# laser.net
KiCad netlist of a schematic drawn in EAGLE
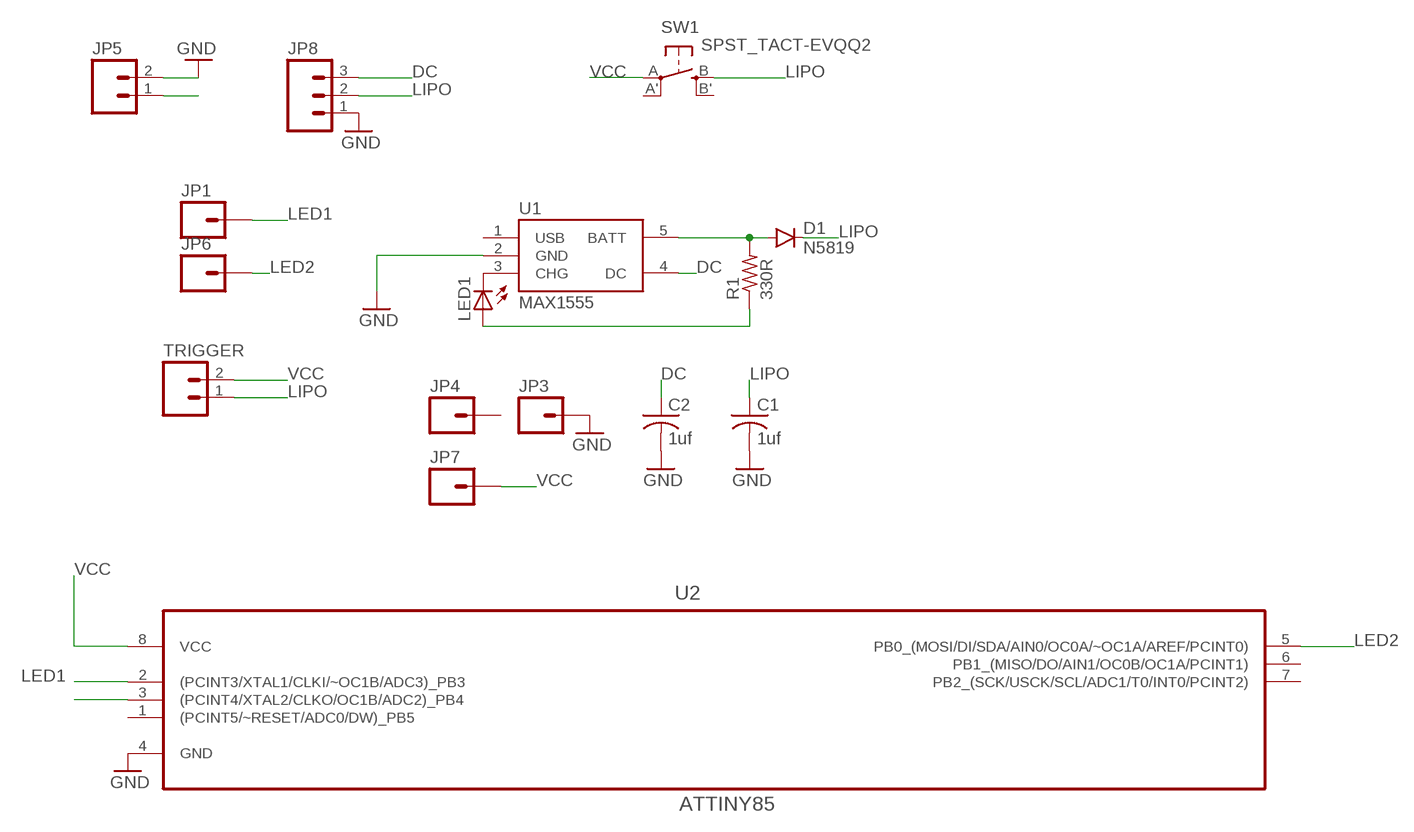
[diagram p0: schematic, sheet 1]

(export (version "E")
  (design (tool "Eeschema 10.0.6"))
  (components
    (comp (ref "C1")
      (value "1uf")
      (footprint "eagle-import:C0805K")
      (libsource (lib "eagle-import") (part "C-USC0805K"))
    )
    (comp (ref "C2")
      (value "1uf")
      (footprint "eagle-import:C0805K")
      (libsource (lib "eagle-import") (part "C-USC0805K"))
    )
    (comp (ref "D1")
      (value "N5819")
      (footprint "eagle-import:DIODE-1N4148")
      (libsource (lib "eagle-import") (part "DIODE1N4148"))
    )
    (comp (ref "JP1")
      (value "M01PTH")
      (footprint "eagle-import:1X01")
      (libsource (lib "eagle-import") (part "M01PTH"))
    )
    (comp (ref "JP3")
      (value "M01PTH")
      (footprint "eagle-import:1X01")
      (libsource (lib "eagle-import") (part "M01PTH"))
    )
    (comp (ref "JP4")
      (value "M01PTH")
      (footprint "eagle-import:1X01")
      (libsource (lib "eagle-import") (part "M01PTH"))
    )
    (comp (ref "JP5")
      (value "M02LOCK")
      (footprint "eagle-import:1X02_LOCK")
      (libsource (lib "eagle-import") (part "M02LOCK"))
    )
    (comp (ref "JP6")
      (value "M01PTH")
      (footprint "eagle-import:1X01")
      (libsource (lib "eagle-import") (part "M01PTH"))
    )
    (comp (ref "JP7")
      (value "M01PTH")
      (footprint "eagle-import:1X01")
      (libsource (lib "eagle-import") (part "M01PTH"))
    )
    (comp (ref "JP8")
      (value "M03LOCK")
      (footprint "eagle-import:1X03_LOCK")
      (libsource (lib "eagle-import") (part "M03LOCK"))
    )
    (comp (ref "LED1")
      (value "LEDCHIP-LED0805")
      (footprint "eagle-import:CHIP-LED0805")
      (libsource (lib "eagle-import") (part "LEDCHIP-LED0805"))
    )
    (comp (ref "R1")
      (value "330R")
      (footprint "eagle-import:M0805")
      (libsource (lib "eagle-import") (part "R-US_M0805"))
    )
    (comp (ref "SW1")
      (value "SPST_TACT-EVQQ2")
      (footprint "eagle-import:EVQ-Q2")
      (libsource (lib "eagle-import") (part "SPST_TACT-EVQQ2"))
    )
    (comp (ref "TRIGGER")
      (value "M02PTH")
      (footprint "eagle-import:1X02")
      (libsource (lib "eagle-import") (part "M02PTH"))
    )
    (comp (ref "U1")
      (value "MAX1555")
      (footprint "eagle-import:SOT23-5")
      (libsource (lib "eagle-import") (part "MAX1555"))
    )
    (comp (ref "U2")
      (value "ATTINY85")
      (footprint "eagle-import:DIP254P762X533-8")
      (fields (field (name "MPN") "ATTINY85-20PU"))
      (libsource (lib "eagle-import") (part "ATTINY85-20PU"))
    )
  )
  (nets
    (net (code "1") (name "/DC") (class "Default")
      (node (ref "C2") (pin "1") (pinfunction "1_1") (pintype "passive"))
      (node (ref "JP8") (pin "3") (pinfunction "3_3") (pintype "passive"))
      (node (ref "U1") (pin "4") (pinfunction "DC_4") (pintype "bidirectional"))
    )
    (net (code "2") (name "/LED1") (class "Default")
      (node (ref "JP1") (pin "1") (pinfunction "1_1") (pintype "passive"))
      (node (ref "U2") (pin "2") (pinfunction "(PCINT3/XTAL1/CLKI/~{OC1B/ADC3})_PB3_2") (pintype "bidirectional"))
    )
    (net (code "3") (name "/LED2") (class "Default")
      (node (ref "JP6") (pin "1") (pinfunction "1_1") (pintype "passive"))
      (node (ref "U2") (pin "5") (pinfunction "PB0_(MOSI/DI/SDA/AIN0/OC0A/~{OC1A/AREF/PCINT0})_5") (pintype "bidirectional"))
    )
    (net (code "4") (name "/LIPO") (class "Default")
      (node (ref "C1") (pin "1") (pinfunction "1_1") (pintype "passive"))
      (node (ref "D1") (pin "C") (pinfunction "C_C") (pintype "passive"))
      (node (ref "JP8") (pin "2") (pinfunction "2_2") (pintype "passive"))
      (node (ref "SW1") (pin "B") (pinfunction "S_B") (pintype "passive"))
      (node (ref "TRIGGER") (pin "1") (pinfunction "1_1") (pintype "passive"))
    )
    (net (code "5") (name "/TONE") (class "Default")
      (node (ref "JP5") (pin "1") (pinfunction "1_1") (pintype "passive"))
      (node (ref "U2") (pin "3") (pinfunction "(PCINT4/XTAL2/CLKO/OC1B/ADC2)_PB4_3") (pintype "bidirectional"))
    )
    (net (code "6") (name "/VCC") (class "Default")
      (node (ref "JP7") (pin "1") (pinfunction "1_1") (pintype "passive"))
      (node (ref "SW1") (pin "A") (pinfunction "P_A") (pintype "passive"))
      (node (ref "TRIGGER") (pin "2") (pinfunction "2_2") (pintype "passive"))
      (node (ref "U2") (pin "8") (pinfunction "VCC_8") (pintype "power_in"))
    )
    (net (code "7") (name "GND") (class "Default")
      (node (ref "C1") (pin "2") (pinfunction "2_2") (pintype "passive"))
      (node (ref "C2") (pin "2") (pinfunction "2_2") (pintype "passive"))
      (node (ref "JP3") (pin "1") (pinfunction "1_1") (pintype "passive"))
      (node (ref "JP5") (pin "2") (pinfunction "2_2") (pintype "passive"))
      (node (ref "JP8") (pin "1") (pinfunction "1_1") (pintype "passive"))
      (node (ref "U1") (pin "2") (pinfunction "GND_2") (pintype "bidirectional"))
      (node (ref "U2") (pin "4") (pinfunction "GND_4") (pintype "passive"))
    )
    (net (code "8") (name "Net-(LED1-PadA)") (class "Default")
      (node (ref "LED1") (pin "A") (pinfunction "A_A") (pintype "passive"))
      (node (ref "R1") (pin "1") (pinfunction "1_1") (pintype "passive"))
    )
    (net (code "9") (name "Net-(U1-BATT)") (class "Default")
      (node (ref "D1") (pin "A") (pinfunction "A_A") (pintype "passive"))
      (node (ref "R1") (pin "2") (pinfunction "2_2") (pintype "passive"))
      (node (ref "U1") (pin "5") (pinfunction "BATT_5") (pintype "bidirectional"))
    )
    (net (code "10") (name "Net-(U1-CHG)") (class "Default")
      (node (ref "LED1") (pin "C") (pinfunction "C_C") (pintype "passive"))
      (node (ref "U1") (pin "3") (pinfunction "CHG_3") (pintype "bidirectional"))
    )
    (net (code "11") (name "unconnected-(JP4-Pad1)") (class "Default")
      (node (ref "JP4") (pin "1") (pinfunction "1_1") (pintype "passive"))
    )
    (net (code "12") (name "unconnected-(SW1-P1-PadA')") (class "Default")
      (node (ref "SW1") (pin "A'") (pinfunction "P1_A'") (pintype "passive"))
    )
    (net (code "13") (name "unconnected-(SW1-S1-PadB')") (class "Default")
      (node (ref "SW1") (pin "B'") (pinfunction "S1_B'") (pintype "passive"))
    )
    (net (code "14") (name "unconnected-(U1-USB-Pad1)") (class "Default")
      (node (ref "U1") (pin "1") (pinfunction "USB_1") (pintype "bidirectional"))
    )
    (net (code "15") (name "unconnected-(U2-(PCINT5{slash}~{RESET{slash}ADC0{slash}DW})_PB5-Pad1)") (class "Default")
      (node (ref "U2") (pin "1") (pinfunction "(PCINT5/~{RESET/ADC0/DW})_PB5_1") (pintype "bidirectional"))
    )
    (net (code "16") (name "unconnected-(U2-PB1_(MISO{slash}DO{slash}AIN1{slash}OC0B{slash}OC1A{slash}PCINT1)-Pad6)") (class "Default")
      (node (ref "U2") (pin "6") (pinfunction "PB1_(MISO/DO/AIN1/OC0B/OC1A/PCINT1)_6") (pintype "bidirectional"))
    )
    (net (code "17") (name "unconnected-(U2-PB2_(SCK{slash}USCK{slash}SCL{slash}ADC1{slash}T0{slash}INT0{slash}PCINT2)-Pad7)") (class "Default")
      (node (ref "U2") (pin "7") (pinfunction "PB2_(SCK/USCK/SCL/ADC1/T0/INT0/PCINT2)_7") (pintype "bidirectional"))
    )
  )
)
